# dsbrut2_2bit.net
KiCad netlist of a schematic drawn in EAGLE
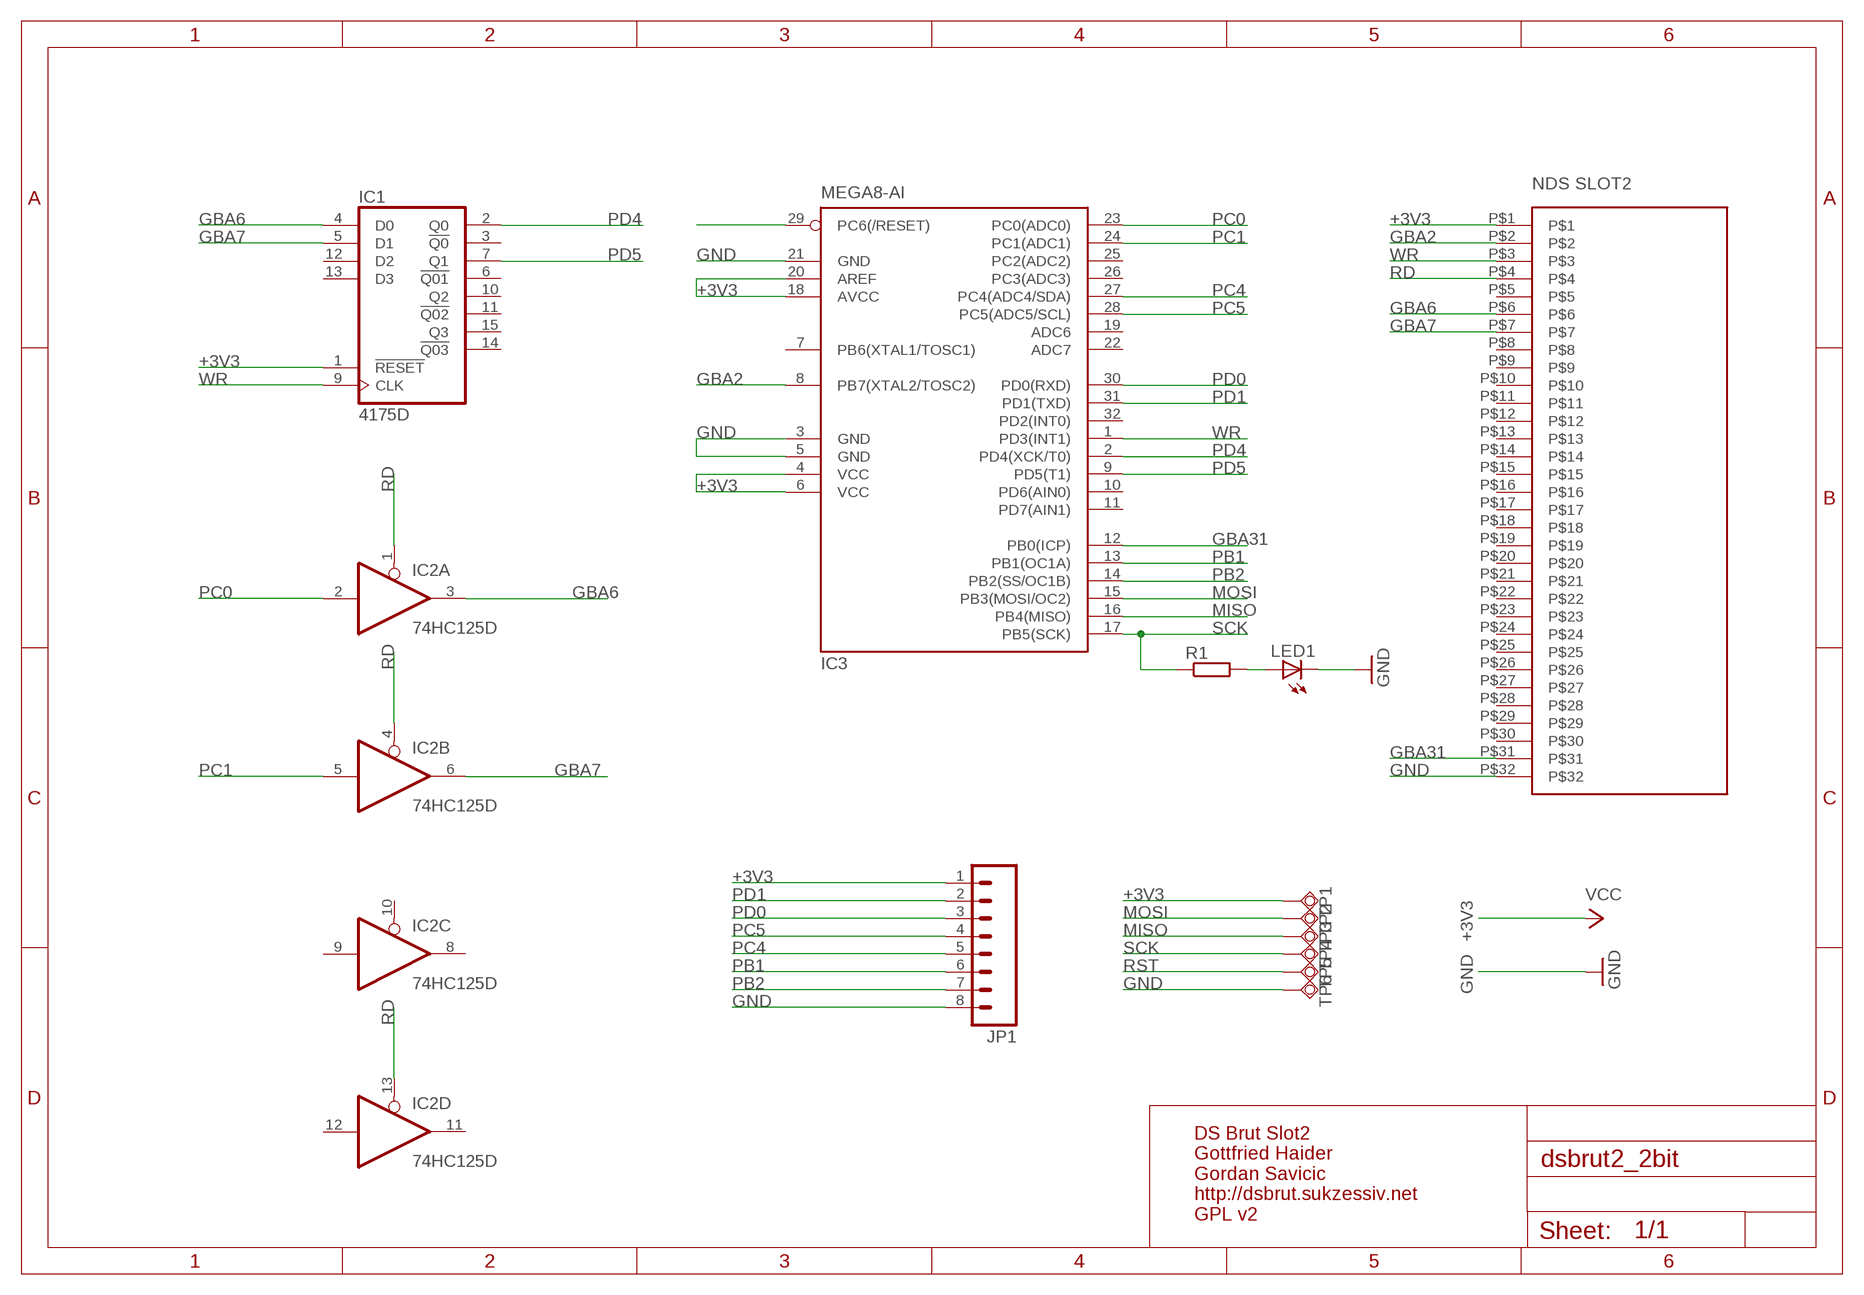
[diagram p0: schematic, sheet 1]

(export (version "E")
  (design (tool "Eeschema 10.0.6"))
  (components
    (comp (ref "IC1")
      (value "4175D")
      (footprint "eagle-import:SO16")
      (libsource (lib "eagle-import") (part "4175D"))
    )
    (comp (ref "IC2")
      (value "74HC125D")
      (footprint "eagle-import:SO14")
      (libsource (lib "eagle-import") (part "74125DHC"))
    )
    (comp (ref "IC3")
      (value "MEGA8-AI")
      (footprint "eagle-import:TQFP32-08")
      (fields (field (name "MPN") "ATMEGA8-16AU"))
      (libsource (lib "eagle-import") (part "MEGA8-AI"))
    )
    (comp (ref "JP1")
      (value "M08LONGPADS")
      (footprint "eagle-import:1X08_LONGPADS")
      (libsource (lib "eagle-import") (part "M08LONGPADS"))
    )
    (comp (ref "LED1")
      (value "LED0603")
      (footprint "eagle-import:LED-0603")
      (libsource (lib "eagle-import") (part "LED0603"))
    )
    (comp (ref "R1")
      (value "R-EU_M0805")
      (footprint "eagle-import:M0805")
      (libsource (lib "eagle-import") (part "R-EU_M0805"))
    )
    (comp (ref "TP1")
      (value "TPSQTP16R")
      (footprint "eagle-import:TP16R")
      (libsource (lib "eagle-import") (part "TPSQTP16R"))
    )
    (comp (ref "TP2")
      (value "TPSQTP16R")
      (footprint "eagle-import:TP16R")
      (libsource (lib "eagle-import") (part "TPSQTP16R"))
    )
    (comp (ref "TP3")
      (value "TPSQTP16R")
      (footprint "eagle-import:TP16R")
      (libsource (lib "eagle-import") (part "TPSQTP16R"))
    )
    (comp (ref "TP4")
      (value "TPSQTP16R")
      (footprint "eagle-import:TP16R")
      (libsource (lib "eagle-import") (part "TPSQTP16R"))
    )
    (comp (ref "TP5")
      (value "TPSQTP16R")
      (footprint "eagle-import:TP16R")
      (libsource (lib "eagle-import") (part "TPSQTP16R"))
    )
    (comp (ref "TP6")
      (value "TPSQTP16R")
      (footprint "eagle-import:TP16R")
      (libsource (lib "eagle-import") (part "TPSQTP16R"))
    )
    (comp (ref "U$1")
      (value "DS_CARTRIDGE_SLOT2")
      (footprint "eagle-import:DS-CARTRIDGE-SLOT2")
      (libsource (lib "eagle-import") (part "DS_CARTRIDGE_SLOT2"))
    )
  )
  (nets
    (net (code "1") (name "/GBA2") (class "Default")
      (node (ref "IC3") (pin "8") (pinfunction "PB7(XTAL2/TOSC2)_8") (pintype "bidirectional"))
      (node (ref "U$1") (pin "P$2") (pinfunction "P$2_P$2") (pintype "bidirectional"))
    )
    (net (code "2") (name "/GBA6") (class "Default")
      (node (ref "IC1") (pin "4") (pinfunction "D0_4") (pintype "input"))
      (node (ref "IC2") (pin "3") (pinfunction "O_3") (pintype "tri_state"))
      (node (ref "U$1") (pin "P$6") (pinfunction "P$6_P$6") (pintype "bidirectional"))
    )
    (net (code "3") (name "/GBA7") (class "Default")
      (node (ref "IC1") (pin "5") (pinfunction "D1_5") (pintype "input"))
      (node (ref "IC2") (pin "6") (pinfunction "O_6") (pintype "tri_state"))
      (node (ref "U$1") (pin "P$7") (pinfunction "P$7_P$7") (pintype "bidirectional"))
    )
    (net (code "4") (name "/GBA31") (class "Default")
      (node (ref "IC3") (pin "12") (pinfunction "PB0(ICP)_12") (pintype "bidirectional"))
      (node (ref "U$1") (pin "P$31") (pinfunction "P$31_P$31") (pintype "bidirectional"))
    )
    (net (code "5") (name "/MISO") (class "Default")
      (node (ref "IC3") (pin "16") (pinfunction "PB4(MISO)_16") (pintype "bidirectional"))
      (node (ref "TP3") (pin "TP") (pinfunction "TP_TP") (pintype "input"))
    )
    (net (code "6") (name "/MOSI") (class "Default")
      (node (ref "IC3") (pin "15") (pinfunction "PB3(MOSI/OC2)_15") (pintype "bidirectional"))
      (node (ref "TP2") (pin "TP") (pinfunction "TP_TP") (pintype "input"))
    )
    (net (code "7") (name "/PB1") (class "Default")
      (node (ref "IC3") (pin "13") (pinfunction "PB1(OC1A)_13") (pintype "bidirectional"))
      (node (ref "JP1") (pin "6") (pinfunction "6_6") (pintype "passive"))
    )
    (net (code "8") (name "/PB2") (class "Default")
      (node (ref "IC3") (pin "14") (pinfunction "PB2(SS/OC1B)_14") (pintype "bidirectional"))
      (node (ref "JP1") (pin "7") (pinfunction "7_7") (pintype "passive"))
    )
    (net (code "9") (name "/PC0") (class "Default")
      (node (ref "IC2") (pin "2") (pinfunction "I_2") (pintype "input"))
      (node (ref "IC3") (pin "23") (pinfunction "PC0(ADC0)_23") (pintype "bidirectional"))
    )
    (net (code "10") (name "/PC1") (class "Default")
      (node (ref "IC2") (pin "5") (pinfunction "I_5") (pintype "input"))
      (node (ref "IC3") (pin "24") (pinfunction "PC1(ADC1)_24") (pintype "bidirectional"))
    )
    (net (code "11") (name "/PC4") (class "Default")
      (node (ref "IC3") (pin "27") (pinfunction "PC4(ADC4/SDA)_27") (pintype "bidirectional"))
      (node (ref "JP1") (pin "5") (pinfunction "5_5") (pintype "passive"))
    )
    (net (code "12") (name "/PC5") (class "Default")
      (node (ref "IC3") (pin "28") (pinfunction "PC5(ADC5/SCL)_28") (pintype "bidirectional"))
      (node (ref "JP1") (pin "4") (pinfunction "4_4") (pintype "passive"))
    )
    (net (code "13") (name "/PD0") (class "Default")
      (node (ref "IC3") (pin "30") (pinfunction "PD0(RXD)_30") (pintype "bidirectional"))
      (node (ref "JP1") (pin "3") (pinfunction "3_3") (pintype "passive"))
    )
    (net (code "14") (name "/PD1") (class "Default")
      (node (ref "IC3") (pin "31") (pinfunction "PD1(TXD)_31") (pintype "bidirectional"))
      (node (ref "JP1") (pin "2") (pinfunction "2_2") (pintype "passive"))
    )
    (net (code "15") (name "/PD4") (class "Default")
      (node (ref "IC1") (pin "2") (pinfunction "Q0_2") (pintype "output"))
      (node (ref "IC3") (pin "2") (pinfunction "PD4(XCK/T0)_2") (pintype "bidirectional"))
    )
    (net (code "16") (name "/PD5") (class "Default")
      (node (ref "IC1") (pin "7") (pinfunction "Q1_7") (pintype "output"))
      (node (ref "IC3") (pin "9") (pinfunction "PD5(T1)_9") (pintype "bidirectional"))
    )
    (net (code "17") (name "/RD") (class "Default")
      (node (ref "IC2") (pin "1") (pinfunction "OE_1") (pintype "input"))
      (node (ref "IC2") (pin "13") (pinfunction "OE_13") (pintype "input"))
      (node (ref "IC2") (pin "4") (pinfunction "OE_4") (pintype "input"))
      (node (ref "U$1") (pin "P$4") (pinfunction "P$4_P$4") (pintype "bidirectional"))
    )
    (net (code "18") (name "/RST") (class "Default")
      (node (ref "IC3") (pin "29") (pinfunction "PC6(/RESET)_29") (pintype "bidirectional"))
      (node (ref "TP5") (pin "TP") (pinfunction "TP_TP") (pintype "input"))
    )
    (net (code "19") (name "/SCK") (class "Default")
      (node (ref "IC3") (pin "17") (pinfunction "PB5(SCK)_17") (pintype "bidirectional"))
      (node (ref "R1") (pin "1") (pinfunction "1_1") (pintype "passive"))
      (node (ref "TP4") (pin "TP") (pinfunction "TP_TP") (pintype "input"))
    )
    (net (code "20") (name "/WR") (class "Default")
      (node (ref "IC1") (pin "9") (pinfunction "CLK_9") (pintype "input"))
      (node (ref "IC3") (pin "1") (pinfunction "PD3(INT1)_1") (pintype "bidirectional"))
      (node (ref "U$1") (pin "P$3") (pinfunction "P$3_P$3") (pintype "bidirectional"))
    )
    (net (code "21") (name "GND") (class "Default")
      (node (ref "IC3") (pin "21") (pinfunction "GND_21") (pintype "power_in"))
      (node (ref "IC3") (pin "3") (pinfunction "GND_3") (pintype "power_in"))
      (node (ref "IC3") (pin "5") (pinfunction "GND_5") (pintype "power_in"))
      (node (ref "JP1") (pin "8") (pinfunction "8_8") (pintype "passive"))
      (node (ref "LED1") (pin "C") (pinfunction "C_C") (pintype "passive"))
      (node (ref "TP6") (pin "TP") (pinfunction "TP_TP") (pintype "input"))
      (node (ref "U$1") (pin "P$32") (pinfunction "P$32_P$32") (pintype "bidirectional"))
    )
    (net (code "22") (name "Net-(LED1-PadA)") (class "Default")
      (node (ref "LED1") (pin "A") (pinfunction "A_A") (pintype "passive"))
      (node (ref "R1") (pin "2") (pinfunction "2_2") (pintype "passive"))
    )
    (net (code "23") (name "VCC") (class "Default")
      (node (ref "IC1") (pin "1") (pinfunction "~{RESET}_1") (pintype "input"))
      (node (ref "IC3") (pin "18") (pinfunction "AVCC_18") (pintype "power_in"))
      (node (ref "IC3") (pin "20") (pinfunction "AREF_20") (pintype "passive"))
      (node (ref "IC3") (pin "4") (pinfunction "VCC_4") (pintype "power_in"))
      (node (ref "IC3") (pin "6") (pinfunction "VCC_6") (pintype "power_in"))
      (node (ref "JP1") (pin "1") (pinfunction "1_1") (pintype "passive"))
      (node (ref "TP1") (pin "TP") (pinfunction "TP_TP") (pintype "input"))
      (node (ref "U$1") (pin "P$1") (pinfunction "P$1_P$1") (pintype "bidirectional"))
    )
    (net (code "24") (name "unconnected-(IC1A-D2-Pad12)") (class "Default")
      (node (ref "IC1") (pin "12") (pinfunction "D2_12") (pintype "input"))
    )
    (net (code "25") (name "unconnected-(IC1A-D3-Pad13)") (class "Default")
      (node (ref "IC1") (pin "13") (pinfunction "D3_13") (pintype "input"))
    )
    (net (code "26") (name "unconnected-(IC1A-Q2-Pad10)") (class "Default")
      (node (ref "IC1") (pin "10") (pinfunction "Q2_10") (pintype "output"))
    )
    (net (code "27") (name "unconnected-(IC1A-Q3-Pad15)") (class "Default")
      (node (ref "IC1") (pin "15") (pinfunction "Q3_15") (pintype "output"))
    )
    (net (code "28") (name "unconnected-(IC1A-~{Q0}-Pad3)") (class "Default")
      (node (ref "IC1") (pin "3") (pinfunction "~{Q0}_3") (pintype "output"))
    )
    (net (code "29") (name "unconnected-(IC1A-~{Q01}-Pad6)") (class "Default")
      (node (ref "IC1") (pin "6") (pinfunction "~{Q01}_6") (pintype "output"))
    )
    (net (code "30") (name "unconnected-(IC1A-~{Q02}-Pad11)") (class "Default")
      (node (ref "IC1") (pin "11") (pinfunction "~{Q02}_11") (pintype "output"))
    )
    (net (code "31") (name "unconnected-(IC1A-~{Q03}-Pad14)") (class "Default")
      (node (ref "IC1") (pin "14") (pinfunction "~{Q03}_14") (pintype "output"))
    )
    (net (code "32") (name "unconnected-(IC2C-I-Pad9)") (class "Default")
      (node (ref "IC2") (pin "9") (pinfunction "I_9") (pintype "input"))
    )
    (net (code "33") (name "unconnected-(IC2C-O-Pad8)") (class "Default")
      (node (ref "IC2") (pin "8") (pinfunction "O_8") (pintype "tri_state"))
    )
    (net (code "34") (name "unconnected-(IC2C-OE-Pad10)") (class "Default")
      (node (ref "IC2") (pin "10") (pinfunction "OE_10") (pintype "input"))
    )
    (net (code "35") (name "unconnected-(IC2D-I-Pad12)") (class "Default")
      (node (ref "IC2") (pin "12") (pinfunction "I_12") (pintype "input"))
    )
    (net (code "36") (name "unconnected-(IC2D-O-Pad11)") (class "Default")
      (node (ref "IC2") (pin "11") (pinfunction "O_11") (pintype "tri_state"))
    )
    (net (code "37") (name "unconnected-(IC3-ADC6-Pad19)") (class "Default")
      (node (ref "IC3") (pin "19") (pinfunction "ADC6_19") (pintype "bidirectional"))
    )
    (net (code "38") (name "unconnected-(IC3-ADC7-Pad22)") (class "Default")
      (node (ref "IC3") (pin "22") (pinfunction "ADC7_22") (pintype "bidirectional"))
    )
    (net (code "39") (name "unconnected-(IC3-PB6(XTAL1{slash}TOSC1)-Pad7)") (class "Default")
      (node (ref "IC3") (pin "7") (pinfunction "PB6(XTAL1/TOSC1)_7") (pintype "bidirectional"))
    )
    (net (code "40") (name "unconnected-(IC3-PC2(ADC2)-Pad25)") (class "Default")
      (node (ref "IC3") (pin "25") (pinfunction "PC2(ADC2)_25") (pintype "bidirectional"))
    )
    (net (code "41") (name "unconnected-(IC3-PC3(ADC3)-Pad26)") (class "Default")
      (node (ref "IC3") (pin "26") (pinfunction "PC3(ADC3)_26") (pintype "bidirectional"))
    )
    (net (code "42") (name "unconnected-(IC3-PD2(INT0)-Pad32)") (class "Default")
      (node (ref "IC3") (pin "32") (pinfunction "PD2(INT0)_32") (pintype "bidirectional"))
    )
    (net (code "43") (name "unconnected-(IC3-PD6(AIN0)-Pad10)") (class "Default")
      (node (ref "IC3") (pin "10") (pinfunction "PD6(AIN0)_10") (pintype "bidirectional"))
    )
    (net (code "44") (name "unconnected-(IC3-PD7(AIN1)-Pad11)") (class "Default")
      (node (ref "IC3") (pin "11") (pinfunction "PD7(AIN1)_11") (pintype "bidirectional"))
    )
    (net (code "45") (name "unconnected-(U$1-PadP$5)") (class "Default")
      (node (ref "U$1") (pin "P$5") (pinfunction "P$5_P$5") (pintype "bidirectional"))
    )
    (net (code "46") (name "unconnected-(U$1-PadP$8)") (class "Default")
      (node (ref "U$1") (pin "P$8") (pinfunction "P$8_P$8") (pintype "bidirectional"))
    )
    (net (code "47") (name "unconnected-(U$1-PadP$9)") (class "Default")
      (node (ref "U$1") (pin "P$9") (pinfunction "P$9_P$9") (pintype "bidirectional"))
    )
    (net (code "48") (name "unconnected-(U$1-PadP$10)") (class "Default")
      (node (ref "U$1") (pin "P$10") (pinfunction "P$10_P$10") (pintype "bidirectional"))
    )
    (net (code "49") (name "unconnected-(U$1-PadP$11)") (class "Default")
      (node (ref "U$1") (pin "P$11") (pinfunction "P$11_P$11") (pintype "bidirectional"))
    )
    (net (code "50") (name "unconnected-(U$1-PadP$12)") (class "Default")
      (node (ref "U$1") (pin "P$12") (pinfunction "P$12_P$12") (pintype "bidirectional"))
    )
    (net (code "51") (name "unconnected-(U$1-PadP$13)") (class "Default")
      (node (ref "U$1") (pin "P$13") (pinfunction "P$13_P$13") (pintype "bidirectional"))
    )
    (net (code "52") (name "unconnected-(U$1-PadP$14)") (class "Default")
      (node (ref "U$1") (pin "P$14") (pinfunction "P$14_P$14") (pintype "bidirectional"))
    )
    (net (code "53") (name "unconnected-(U$1-PadP$15)") (class "Default")
      (node (ref "U$1") (pin "P$15") (pinfunction "P$15_P$15") (pintype "bidirectional"))
    )
    (net (code "54") (name "unconnected-(U$1-PadP$16)") (class "Default")
      (node (ref "U$1") (pin "P$16") (pinfunction "P$16_P$16") (pintype "bidirectional"))
    )
    (net (code "55") (name "unconnected-(U$1-PadP$17)") (class "Default")
      (node (ref "U$1") (pin "P$17") (pinfunction "P$17_P$17") (pintype "bidirectional"))
    )
    (net (code "56") (name "unconnected-(U$1-PadP$18)") (class "Default")
      (node (ref "U$1") (pin "P$18") (pinfunction "P$18_P$18") (pintype "bidirectional"))
    )
    (net (code "57") (name "unconnected-(U$1-PadP$19)") (class "Default")
      (node (ref "U$1") (pin "P$19") (pinfunction "P$19_P$19") (pintype "bidirectional"))
    )
    (net (code "58") (name "unconnected-(U$1-PadP$20)") (class "Default")
      (node (ref "U$1") (pin "P$20") (pinfunction "P$20_P$20") (pintype "bidirectional"))
    )
    (net (code "59") (name "unconnected-(U$1-PadP$21)") (class "Default")
      (node (ref "U$1") (pin "P$21") (pinfunction "P$21_P$21") (pintype "bidirectional"))
    )
    (net (code "60") (name "unconnected-(U$1-PadP$22)") (class "Default")
      (node (ref "U$1") (pin "P$22") (pinfunction "P$22_P$22") (pintype "bidirectional"))
    )
    (net (code "61") (name "unconnected-(U$1-PadP$23)") (class "Default")
      (node (ref "U$1") (pin "P$23") (pinfunction "P$23_P$23") (pintype "bidirectional"))
    )
    (net (code "62") (name "unconnected-(U$1-PadP$24)") (class "Default")
      (node (ref "U$1") (pin "P$24") (pinfunction "P$24_P$24") (pintype "bidirectional"))
    )
    (net (code "63") (name "unconnected-(U$1-PadP$25)") (class "Default")
      (node (ref "U$1") (pin "P$25") (pinfunction "P$25_P$25") (pintype "bidirectional"))
    )
    (net (code "64") (name "unconnected-(U$1-PadP$26)") (class "Default")
      (node (ref "U$1") (pin "P$26") (pinfunction "P$26_P$26") (pintype "bidirectional"))
    )
    (net (code "65") (name "unconnected-(U$1-PadP$27)") (class "Default")
      (node (ref "U$1") (pin "P$27") (pinfunction "P$27_P$27") (pintype "bidirectional"))
    )
    (net (code "66") (name "unconnected-(U$1-PadP$28)") (class "Default")
      (node (ref "U$1") (pin "P$28") (pinfunction "P$28_P$28") (pintype "bidirectional"))
    )
    (net (code "67") (name "unconnected-(U$1-PadP$29)") (class "Default")
      (node (ref "U$1") (pin "P$29") (pinfunction "P$29_P$29") (pintype "bidirectional"))
    )
    (net (code "68") (name "unconnected-(U$1-PadP$30)") (class "Default")
      (node (ref "U$1") (pin "P$30") (pinfunction "P$30_P$30") (pintype "bidirectional"))
    )
  )
)
